# IMU_GNSS.net
KiCad netlist of a schematic drawn in Altium Designer
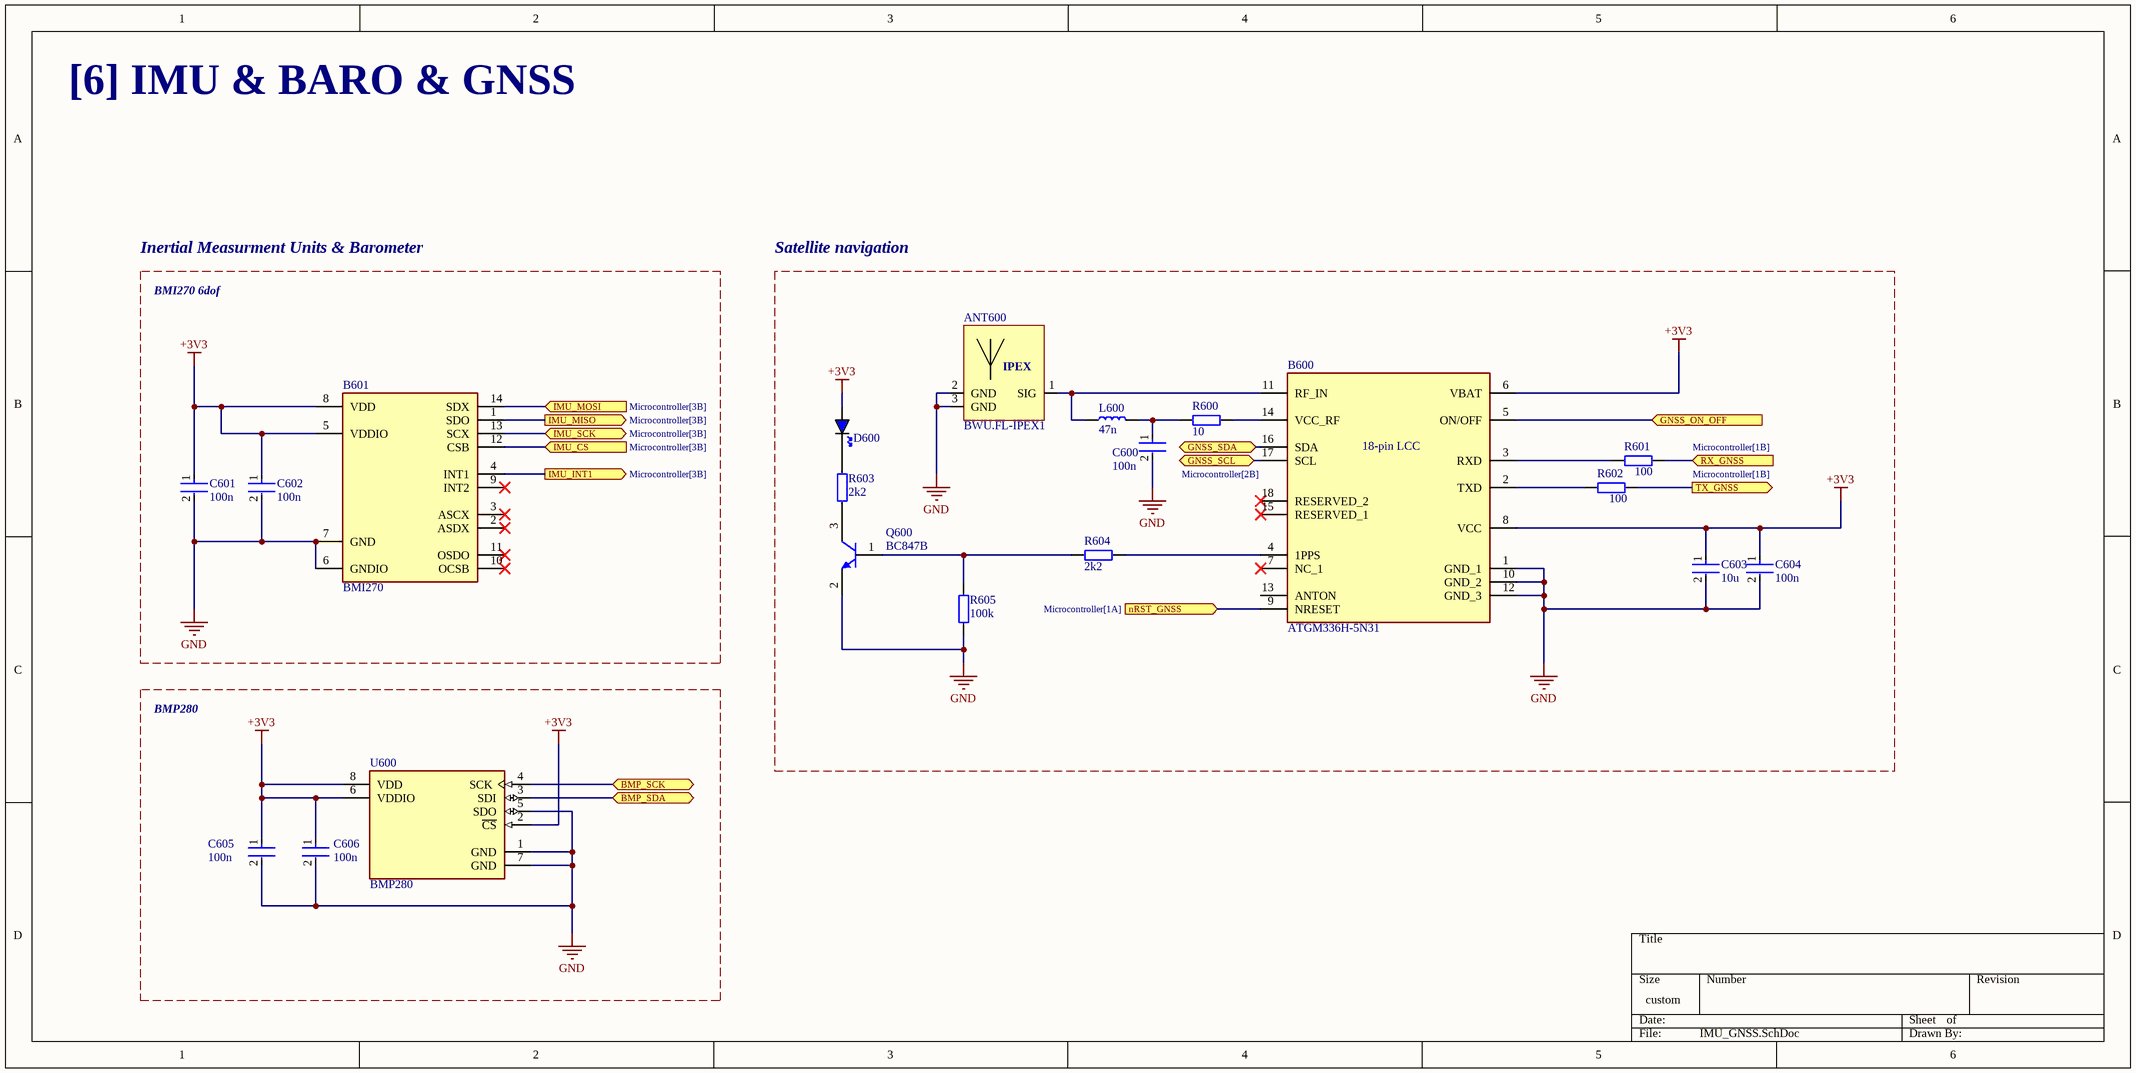
[diagram p0: IMU_GNSS.SchDoc]

(export (version "E")
  (design (tool "Eeschema 10.0.6"))
  (components
    (comp (ref "ANT600")
      (value "BWU.FL-IPEX1")
      (footprint "BWU.FL-IPEX1")
      (description "IPEX conn Antenna 2.4GHz 50Ohm")
      (libsource (lib "SCHEM_FC_NAVC_LIB") (part "BWU.FL-IPEX1"))
    )
    (comp (ref "B600")
      (value "ATGM336H-5N31")
      (footprint "ATGM336H5N31")
      (description "GSM & GPRS & GPS Modules 9.7X10.1mm RoHS")
      (libsource (lib "SCHEM_FC_NAVC_LIB") (part "ATGM336H-5N31"))
    )
    (comp (ref "B601")
      (value "BMI270")
      (footprint "QFN50P300X250X87-14N")
      (fields (field (name "MOUSER PART NUMBER") "262-BMI270"))
      (libsource (lib "SCHEM_FC_NAVC_LIB") (part "BMI270"))
    )
    (comp (ref "C600")
      (value "100n")
      (footprint "FP-CL779-IPC_C")
      (description "Cap Ceramic 100nF 50V X7R ±10% SMD 0402 +125°C Paper T/R CL05B104KB54PNC")
      (libsource (lib "Altium Content Vault") (part "b4654b650e69147ec39a6b967a45e02"))
    )
    (comp (ref "C601")
      (value "100n")
      (footprint "FP-CL779-IPC_C")
      (description "Cap Ceramic 100nF 50V X7R ±10% SMD 0402 +125°C Paper T/R CL05B104KB54PNC")
      (libsource (lib "Altium Content Vault") (part "b4654b650e69147ec39a6b967a45e02"))
    )
    (comp (ref "C602")
      (value "100n")
      (footprint "FP-CL779-IPC_C")
      (description "Cap Ceramic 100nF 50V X7R ±10% SMD 0402 +125°C Paper T/R CL05B104KB54PNC")
      (libsource (lib "Altium Content Vault") (part "b4654b650e69147ec39a6b967a45e02"))
    )
    (comp (ref "C603")
      (value "10u")
      (footprint "FP-CL10-IPC_C")
      (description "Cap Ceramic 10uF 25V X5R ±20% Pad SMD 0603 +85°C T/R")
      (fields (field (name "TOLERANCE") "20%"))
      (libsource (lib "Altium Content Vault") (part "b4654b650e69147ec39a6b967a45e02"))
    )
    (comp (ref "C604")
      (value "100n")
      (footprint "FP-CL779-IPC_C")
      (description "Cap Ceramic 100nF 50V X7R ±10% SMD 0402 +125°C Paper T/R CL05B104KB54PNC")
      (libsource (lib "Altium Content Vault") (part "b4654b650e69147ec39a6b967a45e02"))
    )
    (comp (ref "C605")
      (value "100n")
      (footprint "FP-CL779-IPC_C")
      (description "Cap Ceramic 100nF 50V X7R ±10% SMD 0402 +125°C Paper T/R CL05B104KB54PNC")
      (libsource (lib "Altium Content Vault") (part "b4654b650e69147ec39a6b967a45e02"))
    )
    (comp (ref "C606")
      (value "100n")
      (footprint "FP-CL779-IPC_C")
      (description "Cap Ceramic 100nF 50V X7R ±10% SMD 0402 +125°C Paper T/R CL05B104KB54PNC")
      (libsource (lib "Altium Content Vault") (part "b4654b650e69147ec39a6b967a45e02"))
    )
    (comp (ref "D600")
      (value "BLUE")
      (footprint "LED_0603_BLUE")
      (description "LED 0603 BLUE SMD")
      (libsource (lib "Schematic-Lib-PhilsLab") (part "LED_0603_BLUE"))
    )
    (comp (ref "L600")
      (value "47n")
      (footprint "IND_0603")
      (description "Inductor SMD 0603")
      (libsource (lib "Schematic-Lib-PhilsLab") (part "IND_0603"))
    )
    (comp (ref "Q600")
      (value "BC847B")
      (footprint "INF-SOT23_M")
      (description "NPN Silicon AF Transistor, 45 V VCEO, 100 mA IC, SOT23, Reel, Green")
      (fields (field (name "MANUFACTURER") "Infineon"))
      (libsource (lib "Altium Content Vault") (part "INF-BJTNPN-BEC-3"))
    )
    (comp (ref "R600")
      (value "10")
      (footprint "RES_0603")
      (description "Resistor SMD 0603")
      (libsource (lib "Schematic-Lib-PhilsLab") (part "RES_0603"))
    )
    (comp (ref "R601")
      (value "100")
      (footprint "RES_0603")
      (description "Resistor SMD 0603")
      (libsource (lib "Schematic-Lib-PhilsLab") (part "RES_0603"))
    )
    (comp (ref "R602")
      (value "100")
      (footprint "RES_0603")
      (description "Resistor SMD 0603")
      (libsource (lib "Schematic-Lib-PhilsLab") (part "RES_0603"))
    )
    (comp (ref "R603")
      (value "2k2")
      (footprint "RES_0603")
      (description "Resistor SMD 0603")
      (libsource (lib "Schematic-Lib-PhilsLab") (part "RES_0603"))
    )
    (comp (ref "R604")
      (value "2k2")
      (footprint "RES_0603")
      (description "Resistor SMD 0603")
      (libsource (lib "Schematic-Lib-PhilsLab") (part "RES_0603"))
    )
    (comp (ref "R605")
      (value "100k")
      (footprint "RES_0603")
      (description "Resistor SMD 0603")
      (libsource (lib "Schematic-Lib-PhilsLab") (part "RES_0603"))
    )
    (comp (ref "U600")
      (value "BMP280")
      (footprint "FP-BMP280-MFG")
      (description "SENSOR PRESSURE ABS")
      (libsource (lib "Altium Content Vault") (part "69b1aacbb03d82763a43fac02afba64"))
    )
  )
  (nets
    (net (code "1") (name "+3V3") (class "Default")
      (node (ref "B600") (pin "6") (pinfunction "VBAT_6") (pintype "passive"))
      (node (ref "B600") (pin "8") (pinfunction "VCC_8") (pintype "passive"))
      (node (ref "B601") (pin "5") (pinfunction "VDDIO_5") (pintype "passive"))
      (node (ref "B601") (pin "8") (pinfunction "VDD_8") (pintype "passive"))
      (node (ref "C601") (pin "1") (pinfunction "1_1") (pintype "passive"))
      (node (ref "C602") (pin "1") (pinfunction "1_1") (pintype "passive"))
      (node (ref "C603") (pin "1") (pinfunction "1_1") (pintype "passive"))
      (node (ref "C604") (pin "1") (pinfunction "1_1") (pintype "passive"))
      (node (ref "C605") (pin "1") (pinfunction "1_1") (pintype "passive"))
      (node (ref "C606") (pin "1") (pinfunction "1_1") (pintype "passive"))
      (node (ref "D600") (pin "A") (pinfunction "A_A") (pintype "passive"))
      (node (ref "U600") (pin "2") (pinfunction "~{CS}_2") (pintype "input"))
      (node (ref "U600") (pin "6") (pinfunction "VDDIO_6") (pintype "power_in"))
      (node (ref "U600") (pin "8") (pinfunction "VDD_8") (pintype "power_in"))
    )
    (net (code "2") (name "/BMP_SCK") (class "Default")
      (node (ref "U600") (pin "4") (pinfunction "SCK_4") (pintype "input"))
    )
    (net (code "3") (name "/BMP_SDA") (class "Default")
      (node (ref "U600") (pin "3") (pinfunction "SDI_3") (pintype "bidirectional"))
    )
    (net (code "4") (name "/GNSS_ON_OFF") (class "Default")
      (node (ref "B600") (pin "5") (pinfunction "ON/OFF_5") (pintype "passive"))
    )
    (net (code "5") (name "/GNSS_SCL") (class "Default")
      (node (ref "B600") (pin "17") (pinfunction "SCL_17") (pintype "passive"))
    )
    (net (code "6") (name "/GNSS_SDA") (class "Default")
      (node (ref "B600") (pin "16") (pinfunction "SDA_16") (pintype "passive"))
    )
    (net (code "7") (name "/IMU_CS") (class "Default")
      (node (ref "B601") (pin "12") (pinfunction "CSB_12") (pintype "passive"))
    )
    (net (code "8") (name "/IMU_INT1") (class "Default")
      (node (ref "B601") (pin "4") (pinfunction "INT1_4") (pintype "passive"))
    )
    (net (code "9") (name "/IMU_MISO") (class "Default")
      (node (ref "B601") (pin "1") (pinfunction "SDO_1") (pintype "passive"))
    )
    (net (code "10") (name "/IMU_MOSI") (class "Default")
      (node (ref "B601") (pin "14") (pinfunction "SDX_14") (pintype "passive"))
    )
    (net (code "11") (name "/IMU_SCK") (class "Default")
      (node (ref "B601") (pin "13") (pinfunction "SCX_13") (pintype "passive"))
    )
    (net (code "12") (name "/RX_GNSS") (class "Default")
      (node (ref "R601") (pin "2") (pinfunction "2_2") (pintype "passive"))
    )
    (net (code "13") (name "/TX_GNSS") (class "Default")
      (node (ref "R602") (pin "2") (pinfunction "2_2") (pintype "passive"))
    )
    (net (code "14") (name "/nRST_GNSS") (class "Default")
      (node (ref "B600") (pin "9") (pinfunction "NRESET_9") (pintype "passive"))
    )
    (net (code "15") (name "GND") (class "Default")
      (node (ref "ANT600") (pin "2") (pinfunction "GND_2") (pintype "power_in"))
      (node (ref "ANT600") (pin "3") (pinfunction "GND_3") (pintype "power_in"))
      (node (ref "B600") (pin "1") (pinfunction "GND_1_1") (pintype "passive"))
      (node (ref "B600") (pin "10") (pinfunction "GND_2_10") (pintype "passive"))
      (node (ref "B600") (pin "12") (pinfunction "GND_3_12") (pintype "passive"))
      (node (ref "B601") (pin "6") (pinfunction "GNDIO_6") (pintype "passive"))
      (node (ref "B601") (pin "7") (pinfunction "GND_7") (pintype "passive"))
      (node (ref "C600") (pin "2") (pinfunction "2_2") (pintype "passive"))
      (node (ref "C601") (pin "2") (pinfunction "2_2") (pintype "passive"))
      (node (ref "C602") (pin "2") (pinfunction "2_2") (pintype "passive"))
      (node (ref "C603") (pin "2") (pinfunction "2_2") (pintype "passive"))
      (node (ref "C604") (pin "2") (pinfunction "2_2") (pintype "passive"))
      (node (ref "C605") (pin "2") (pinfunction "2_2") (pintype "passive"))
      (node (ref "C606") (pin "2") (pinfunction "2_2") (pintype "passive"))
      (node (ref "Q600") (pin "2") (pinfunction "E_2") (pintype "passive"))
      (node (ref "R605") (pin "1") (pinfunction "1_1") (pintype "passive"))
      (node (ref "U600") (pin "1") (pinfunction "GND_1") (pintype "power_in"))
      (node (ref "U600") (pin "5") (pinfunction "SDO_5") (pintype "bidirectional"))
      (node (ref "U600") (pin "7") (pinfunction "GND_7") (pintype "power_in"))
    )
    (net (code "16") (name "Net-(ANT600-SIG)") (class "Default")
      (node (ref "ANT600") (pin "1") (pinfunction "SIG_1") (pintype "passive"))
      (node (ref "B600") (pin "11") (pinfunction "RF_IN_11") (pintype "passive"))
      (node (ref "L600") (pin "1") (pinfunction "1_1") (pintype "passive"))
    )
    (net (code "17") (name "Net-(B600-1PPS)") (class "Default")
      (node (ref "B600") (pin "4") (pinfunction "1PPS_4") (pintype "passive"))
      (node (ref "R604") (pin "2") (pinfunction "2_2") (pintype "passive"))
    )
    (net (code "18") (name "Net-(B600-RXD)") (class "Default")
      (node (ref "B600") (pin "3") (pinfunction "RXD_3") (pintype "passive"))
      (node (ref "R601") (pin "1") (pinfunction "1_1") (pintype "passive"))
    )
    (net (code "19") (name "Net-(B600-TXD)") (class "Default")
      (node (ref "B600") (pin "2") (pinfunction "TXD_2") (pintype "passive"))
      (node (ref "R602") (pin "1") (pinfunction "1_1") (pintype "passive"))
    )
    (net (code "20") (name "Net-(B600-VCC_RF)") (class "Default")
      (node (ref "B600") (pin "14") (pinfunction "VCC_RF_14") (pintype "passive"))
      (node (ref "R600") (pin "2") (pinfunction "2_2") (pintype "passive"))
    )
    (net (code "21") (name "Net-(C600-Pad1)") (class "Default")
      (node (ref "C600") (pin "1") (pinfunction "1_1") (pintype "passive"))
      (node (ref "L600") (pin "2") (pinfunction "2_2") (pintype "passive"))
      (node (ref "R600") (pin "1") (pinfunction "1_1") (pintype "passive"))
    )
    (net (code "22") (name "Net-(D600-PadK)") (class "Default")
      (node (ref "D600") (pin "K") (pinfunction "K_K") (pintype "passive"))
      (node (ref "R603") (pin "2") (pinfunction "2_2") (pintype "passive"))
    )
    (net (code "23") (name "Net-(Q600-B)") (class "Default")
      (node (ref "Q600") (pin "1") (pinfunction "B_1") (pintype "passive"))
      (node (ref "R604") (pin "1") (pinfunction "1_1") (pintype "passive"))
      (node (ref "R605") (pin "2") (pinfunction "2_2") (pintype "passive"))
    )
    (net (code "24") (name "Net-(Q600-C)") (class "Default")
      (node (ref "Q600") (pin "3") (pinfunction "C_3") (pintype "passive"))
      (node (ref "R603") (pin "1") (pinfunction "1_1") (pintype "passive"))
    )
    (net (code "25") (name "unconnected-(B600-ANTON-Pad13)") (class "Default")
      (node (ref "B600") (pin "13") (pinfunction "ANTON_13") (pintype "passive"))
    )
    (net (code "26") (name "unconnected-(B600-NC_1-Pad7)") (class "Default")
      (node (ref "B600") (pin "7") (pinfunction "NC_1_7") (pintype "passive+no_connect"))
    )
    (net (code "27") (name "unconnected-(B600-RESERVED_1-Pad15)") (class "Default")
      (node (ref "B600") (pin "15") (pinfunction "RESERVED_1_15") (pintype "passive+no_connect"))
    )
    (net (code "28") (name "unconnected-(B600-RESERVED_2-Pad18)") (class "Default")
      (node (ref "B600") (pin "18") (pinfunction "RESERVED_2_18") (pintype "passive+no_connect"))
    )
    (net (code "29") (name "unconnected-(B601-ASCX-Pad3)") (class "Default")
      (node (ref "B601") (pin "3") (pinfunction "ASCX_3") (pintype "passive+no_connect"))
    )
    (net (code "30") (name "unconnected-(B601-ASDX-Pad2)") (class "Default")
      (node (ref "B601") (pin "2") (pinfunction "ASDX_2") (pintype "passive+no_connect"))
    )
    (net (code "31") (name "unconnected-(B601-INT2-Pad9)") (class "Default")
      (node (ref "B601") (pin "9") (pinfunction "INT2_9") (pintype "passive+no_connect"))
    )
    (net (code "32") (name "unconnected-(B601-OCSB-Pad10)") (class "Default")
      (node (ref "B601") (pin "10") (pinfunction "OCSB_10") (pintype "passive+no_connect"))
    )
    (net (code "33") (name "unconnected-(B601-OSDO-Pad11)") (class "Default")
      (node (ref "B601") (pin "11") (pinfunction "OSDO_11") (pintype "passive+no_connect"))
    )
  )
)
